# Control_board.net
KiCad netlist of a schematic drawn in Altium Designer
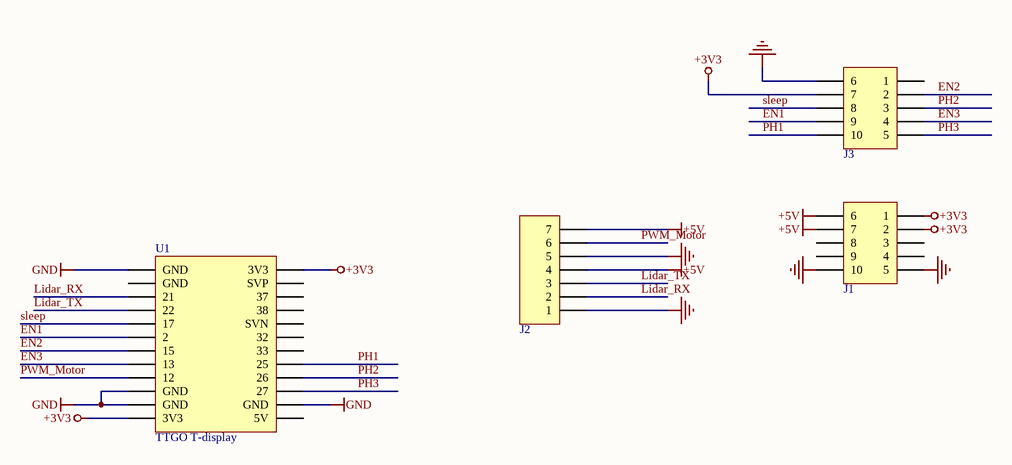
[diagram p0: Control_board.SchDoc]

(export (version "E")
  (design (tool "Eeschema 10.0.6"))
  (components
    (comp (ref "J1")
      (value "10p")
      (footprint "61301021121")
      (description "WR-PHD 2.54 mm THT Dual Pin Header, 10p")
      (fields (field (name "PART NUMBER") "61301021121"))
      (libsource (lib "Male_header_254mm") (part "61301021121"))
    )
    (comp (ref "J2")
      (value "07p")
      (footprint "61300711121")
      (description "WR-PHD 2.54 mm THT Pin Header, 07p")
      (fields (field (name "PART NUMBER") "61300711121"))
      (libsource (lib "Male_header_254mm") (part "61300711121"))
    )
    (comp (ref "J3")
      (value "10p")
      (footprint "61301021121")
      (description "WR-PHD 2.54 mm THT Dual Pin Header, 10p")
      (fields (field (name "PART NUMBER") "61301021121"))
      (libsource (lib "Male_header_254mm") (part "61301021121"))
    )
    (comp (ref "U1")
      (value "TTGO T-display")
      (footprint "ESP32-TTGO-TDISPLAY")
      (libsource (lib "TE") (part "TTGO T-display"))
    )
  )
  (nets
    (net (code "1") (name "+3V3") (class "Default")
      (node (ref "J1") (pin "1") (pinfunction "1_1") (pintype "passive"))
      (node (ref "J1") (pin "2") (pinfunction "2_2") (pintype "passive"))
      (node (ref "J3") (pin "7") (pinfunction "7_7") (pintype "passive"))
      (node (ref "U1") (pin "3V3") (pinfunction "3V3_3V3") (pintype "passive"))
      (node (ref "U1") (pin "3V3-") (pinfunction "3V3_3V3-") (pintype "passive"))
    )
    (net (code "2") (name "+5V") (class "Default")
      (node (ref "J1") (pin "6") (pinfunction "6_6") (pintype "passive"))
      (node (ref "J1") (pin "7") (pinfunction "7_7") (pintype "passive"))
      (node (ref "J2") (pin "4") (pinfunction "4_4") (pintype "passive"))
      (node (ref "J2") (pin "7") (pinfunction "7_7") (pintype "passive"))
    )
    (net (code "3") (name "/EN1") (class "Default")
      (node (ref "J3") (pin "9") (pinfunction "9_9") (pintype "passive"))
      (node (ref "U1") (pin "2") (pinfunction "2_2") (pintype "passive"))
    )
    (net (code "4") (name "/EN2") (class "Default")
      (node (ref "J3") (pin "2") (pinfunction "2_2") (pintype "passive"))
      (node (ref "U1") (pin "15") (pinfunction "15_15") (pintype "passive"))
    )
    (net (code "5") (name "/EN3") (class "Default")
      (node (ref "J3") (pin "4") (pinfunction "4_4") (pintype "passive"))
      (node (ref "U1") (pin "13") (pinfunction "13_13") (pintype "passive"))
    )
    (net (code "6") (name "/Lidar_RX") (class "Default")
      (node (ref "J2") (pin "2") (pinfunction "2_2") (pintype "passive"))
      (node (ref "U1") (pin "21") (pinfunction "21_21") (pintype "passive"))
    )
    (net (code "7") (name "/Lidar_TX") (class "Default")
      (node (ref "J2") (pin "3") (pinfunction "3_3") (pintype "passive"))
      (node (ref "U1") (pin "22") (pinfunction "22_22") (pintype "passive"))
    )
    (net (code "8") (name "/PH1") (class "Default")
      (node (ref "J3") (pin "10") (pinfunction "10_10") (pintype "passive"))
      (node (ref "U1") (pin "25") (pinfunction "25_25") (pintype "passive"))
    )
    (net (code "9") (name "/PH2") (class "Default")
      (node (ref "J3") (pin "3") (pinfunction "3_3") (pintype "passive"))
      (node (ref "U1") (pin "26") (pinfunction "26_26") (pintype "passive"))
    )
    (net (code "10") (name "/PH3") (class "Default")
      (node (ref "J3") (pin "5") (pinfunction "5_5") (pintype "passive"))
      (node (ref "U1") (pin "27") (pinfunction "27_27") (pintype "passive"))
    )
    (net (code "11") (name "/PWM_Motor") (class "Default")
      (node (ref "J2") (pin "6") (pinfunction "6_6") (pintype "passive"))
      (node (ref "U1") (pin "12") (pinfunction "12_12") (pintype "passive"))
    )
    (net (code "12") (name "/sleep") (class "Default")
      (node (ref "J3") (pin "8") (pinfunction "8_8") (pintype "passive"))
      (node (ref "U1") (pin "17") (pinfunction "17_17") (pintype "passive"))
    )
    (net (code "13") (name "GND") (class "Default")
      (node (ref "J1") (pin "10") (pinfunction "10_10") (pintype "passive"))
      (node (ref "J1") (pin "5") (pinfunction "5_5") (pintype "passive"))
      (node (ref "J2") (pin "1") (pinfunction "1_1") (pintype "passive"))
      (node (ref "J2") (pin "5") (pinfunction "5_5") (pintype "passive"))
      (node (ref "J3") (pin "6") (pinfunction "6_6") (pintype "passive"))
      (node (ref "U1") (pin "GND1") (pinfunction "GND_GND1") (pintype "passive"))
      (node (ref "U1") (pin "GND3") (pinfunction "GND_GND3") (pintype "passive"))
      (node (ref "U1") (pin "GND4") (pinfunction "GND_GND4") (pintype "passive"))
      (node (ref "U1") (pin "GND5") (pinfunction "GND_GND5") (pintype "passive"))
    )
    (net (code "14") (name "unconnected-(J1-Pad3)") (class "Default")
      (node (ref "J1") (pin "3") (pinfunction "3_3") (pintype "passive"))
    )
    (net (code "15") (name "unconnected-(J1-Pad4)") (class "Default")
      (node (ref "J1") (pin "4") (pinfunction "4_4") (pintype "passive"))
    )
    (net (code "16") (name "unconnected-(J1-Pad8)") (class "Default")
      (node (ref "J1") (pin "8") (pinfunction "8_8") (pintype "passive"))
    )
    (net (code "17") (name "unconnected-(J1-Pad9)") (class "Default")
      (node (ref "J1") (pin "9") (pinfunction "9_9") (pintype "passive"))
    )
    (net (code "18") (name "unconnected-(J3-Pad1)") (class "Default")
      (node (ref "J3") (pin "1") (pinfunction "1_1") (pintype "passive"))
    )
    (net (code "19") (name "unconnected-(U1-GND-PadGND2)") (class "Default")
      (node (ref "U1") (pin "GND2") (pinfunction "GND_GND2") (pintype "passive"))
    )
    (net (code "20") (name "unconnected-(U1-Pad5V)") (class "Default")
      (node (ref "U1") (pin "5V") (pinfunction "5V_5V") (pintype "passive"))
    )
    (net (code "21") (name "unconnected-(U1-Pad32)") (class "Default")
      (node (ref "U1") (pin "32") (pinfunction "32_32") (pintype "passive"))
    )
    (net (code "22") (name "unconnected-(U1-Pad33)") (class "Default")
      (node (ref "U1") (pin "33") (pinfunction "33_33") (pintype "passive"))
    )
    (net (code "23") (name "unconnected-(U1-Pad37)") (class "Default")
      (node (ref "U1") (pin "37") (pinfunction "37_37") (pintype "passive"))
    )
    (net (code "24") (name "unconnected-(U1-Pad38)") (class "Default")
      (node (ref "U1") (pin "38") (pinfunction "38_38") (pintype "passive"))
    )
    (net (code "25") (name "unconnected-(U1-PadSVN)") (class "Default")
      (node (ref "U1") (pin "SVN") (pinfunction "SVN_SVN") (pintype "passive"))
    )
    (net (code "26") (name "unconnected-(U1-PadSVP)") (class "Default")
      (node (ref "U1") (pin "SVP") (pinfunction "SVP_SVP") (pintype "passive"))
    )
  )
)
